# combo_board.net
KiCad netlist of a schematic drawn in EAGLE
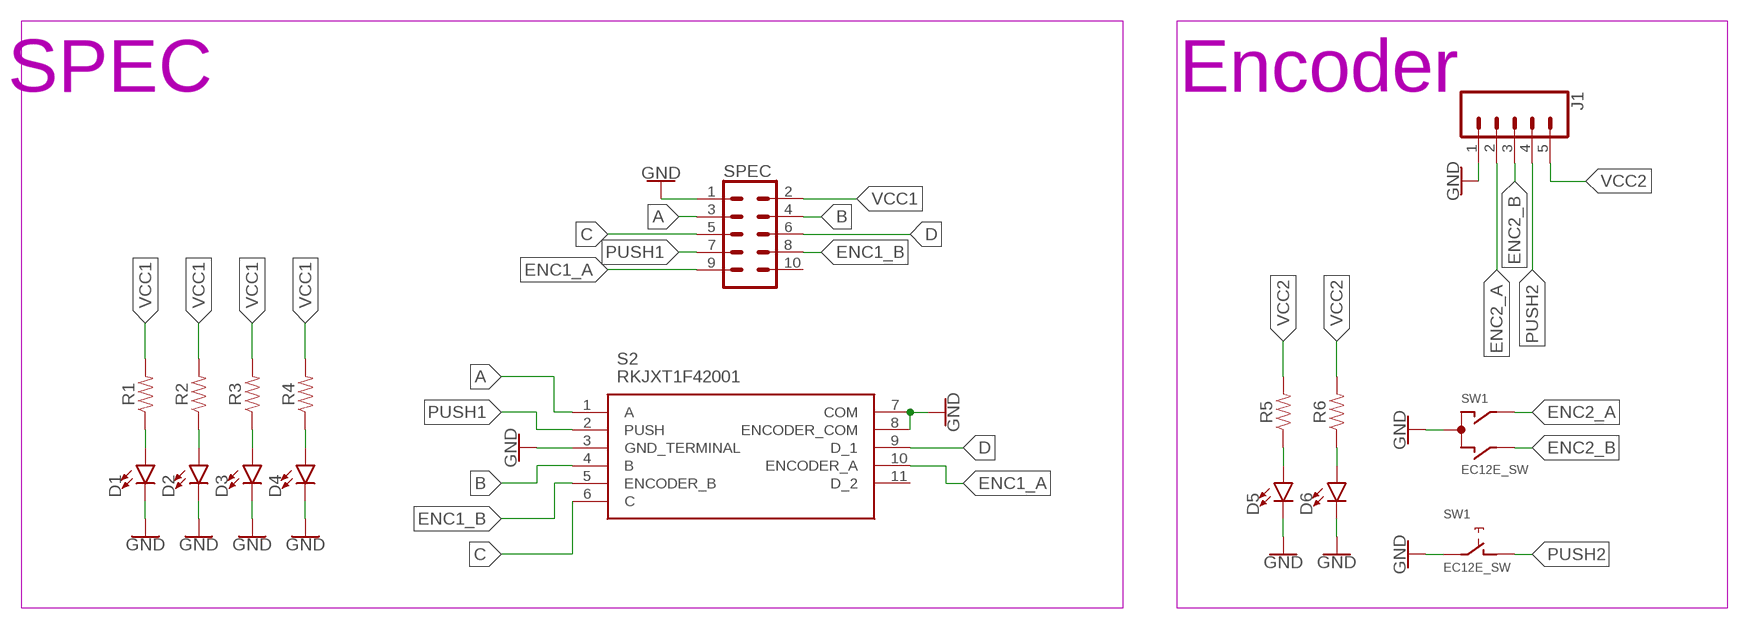
[diagram p0: schematic, sheet 1]

(export (version "E")
  (design (tool "Eeschema 10.0.6"))
  (components
    (comp (ref "D1")
      (value "LED-3MM-NO_SILK")
      (footprint "eagle-import:LED_3MM-NS")
      (libsource (lib "eagle-import") (part "LED-3MM-NO_SILK"))
    )
    (comp (ref "D2")
      (value "LED-3MM-NO_SILK")
      (footprint "eagle-import:LED_3MM-NS")
      (libsource (lib "eagle-import") (part "LED-3MM-NO_SILK"))
    )
    (comp (ref "D3")
      (value "LED-3MM-NO_SILK")
      (footprint "eagle-import:LED_3MM-NS")
      (libsource (lib "eagle-import") (part "LED-3MM-NO_SILK"))
    )
    (comp (ref "D4")
      (value "LED-3MM-NO_SILK")
      (footprint "eagle-import:LED_3MM-NS")
      (libsource (lib "eagle-import") (part "LED-3MM-NO_SILK"))
    )
    (comp (ref "D5")
      (value "LED-3MM-NO_SILK")
      (footprint "eagle-import:LED_3MM-NS")
      (libsource (lib "eagle-import") (part "LED-3MM-NO_SILK"))
    )
    (comp (ref "D6")
      (value "LED-3MM-NO_SILK")
      (footprint "eagle-import:LED_3MM-NS")
      (libsource (lib "eagle-import") (part "LED-3MM-NO_SILK"))
    )
    (comp (ref "J1")
      (value "CONN_05")
      (footprint "eagle-import:1X05")
      (libsource (lib "eagle-import") (part "CONN_05"))
    )
    (comp (ref "R1")
      (value "RESISTOR1206")
      (footprint "eagle-import:1206")
      (libsource (lib "eagle-import") (part "RESISTOR1206"))
    )
    (comp (ref "R2")
      (value "RESISTOR1206")
      (footprint "eagle-import:1206")
      (libsource (lib "eagle-import") (part "RESISTOR1206"))
    )
    (comp (ref "R3")
      (value "RESISTOR1206")
      (footprint "eagle-import:1206")
      (libsource (lib "eagle-import") (part "RESISTOR1206"))
    )
    (comp (ref "R4")
      (value "RESISTOR1206")
      (footprint "eagle-import:1206")
      (libsource (lib "eagle-import") (part "RESISTOR1206"))
    )
    (comp (ref "R5")
      (value "RESISTOR1206")
      (footprint "eagle-import:1206")
      (libsource (lib "eagle-import") (part "RESISTOR1206"))
    )
    (comp (ref "R6")
      (value "RESISTOR1206")
      (footprint "eagle-import:1206")
      (libsource (lib "eagle-import") (part "RESISTOR1206"))
    )
    (comp (ref "S2")
      (value "RKJXT1F42001")
      (footprint "eagle-import:RKJXT1F42001")
      (fields
        (field (name "MOUSER_PART_NUMBER") "688-RKJXT1F42001")
        (field (name "RS_PART_NUMBER") "1239636")
      )
      (libsource (lib "eagle-import") (part "RKJXT1F42001"))
    )
    (comp (ref "SPEC")
      (value "CONN_05X2PTH")
      (footprint "eagle-import:2X5")
      (libsource (lib "eagle-import") (part "CONN_05X2PTH"))
    )
    (comp (ref "SW1")
      (value "EC12E_SW")
      (footprint "eagle-import:ALPS_EC12E_SW")
      (fields (field (name "MPN") "EC12E2424407"))
      (libsource (lib "eagle-import") (part "EC12E_SW"))
    )
  )
  (nets
    (net (code "1") (name "A") (class "Default")
      (node (ref "S2") (pin "1") (pinfunction "A_1") (pintype "bidirectional"))
      (node (ref "SPEC") (pin "3") (pinfunction "3_3") (pintype "passive"))
    )
    (net (code "2") (name "B") (class "Default")
      (node (ref "S2") (pin "4") (pinfunction "B_4") (pintype "bidirectional"))
      (node (ref "SPEC") (pin "4") (pinfunction "4_4") (pintype "passive"))
    )
    (net (code "3") (name "C") (class "Default")
      (node (ref "S2") (pin "6") (pinfunction "C_6") (pintype "bidirectional"))
      (node (ref "SPEC") (pin "5") (pinfunction "5_5") (pintype "passive"))
    )
    (net (code "4") (name "D") (class "Default")
      (node (ref "S2") (pin "9") (pinfunction "D_1_9") (pintype "bidirectional"))
      (node (ref "SPEC") (pin "6") (pinfunction "6_6") (pintype "passive"))
    )
    (net (code "5") (name "ENC1_A") (class "Default")
      (node (ref "S2") (pin "10") (pinfunction "ENCODER_A_10") (pintype "bidirectional"))
      (node (ref "SPEC") (pin "9") (pinfunction "9_9") (pintype "passive"))
    )
    (net (code "6") (name "ENC1_B") (class "Default")
      (node (ref "S2") (pin "5") (pinfunction "ENCODER_B_5") (pintype "bidirectional"))
      (node (ref "SPEC") (pin "8") (pinfunction "8_8") (pintype "passive"))
    )
    (net (code "7") (name "ENC2_A") (class "Default")
      (node (ref "J1") (pin "2") (pinfunction "2_2") (pintype "passive"))
      (node (ref "SW1") (pin "A") (pinfunction "A_A") (pintype "passive"))
    )
    (net (code "8") (name "ENC2_B") (class "Default")
      (node (ref "J1") (pin "3") (pinfunction "3_3") (pintype "passive"))
      (node (ref "SW1") (pin "B") (pinfunction "B_B") (pintype "passive"))
    )
    (net (code "9") (name "GND") (class "Default")
      (node (ref "D1") (pin "K") (pinfunction "C_K") (pintype "passive"))
      (node (ref "D2") (pin "K") (pinfunction "C_K") (pintype "passive"))
      (node (ref "D3") (pin "K") (pinfunction "C_K") (pintype "passive"))
      (node (ref "D4") (pin "K") (pinfunction "C_K") (pintype "passive"))
      (node (ref "D5") (pin "K") (pinfunction "C_K") (pintype "passive"))
      (node (ref "D6") (pin "K") (pinfunction "C_K") (pintype "passive"))
      (node (ref "J1") (pin "1") (pinfunction "1_1") (pintype "passive"))
      (node (ref "S2") (pin "3") (pinfunction "GND_TERMINAL_3") (pintype "bidirectional"))
      (node (ref "S2") (pin "7") (pinfunction "COM_7") (pintype "bidirectional"))
      (node (ref "S2") (pin "8") (pinfunction "ENCODER_COM_8") (pintype "bidirectional"))
      (node (ref "SPEC") (pin "1") (pinfunction "1_1") (pintype "passive"))
      (node (ref "SW1") (pin "C") (pinfunction "C_C") (pintype "passive"))
      (node (ref "SW1") (pin "E") (pinfunction "2_E") (pintype "passive"))
    )
    (net (code "10") (name "Net-(D1-PadA)") (class "Default")
      (node (ref "D1") (pin "A") (pinfunction "A_A") (pintype "passive"))
      (node (ref "R1") (pin "1") (pinfunction "1_1") (pintype "passive"))
    )
    (net (code "11") (name "Net-(D2-PadA)") (class "Default")
      (node (ref "D2") (pin "A") (pinfunction "A_A") (pintype "passive"))
      (node (ref "R2") (pin "1") (pinfunction "1_1") (pintype "passive"))
    )
    (net (code "12") (name "Net-(D3-PadA)") (class "Default")
      (node (ref "D3") (pin "A") (pinfunction "A_A") (pintype "passive"))
      (node (ref "R3") (pin "1") (pinfunction "1_1") (pintype "passive"))
    )
    (net (code "13") (name "Net-(D4-PadA)") (class "Default")
      (node (ref "D4") (pin "A") (pinfunction "A_A") (pintype "passive"))
      (node (ref "R4") (pin "1") (pinfunction "1_1") (pintype "passive"))
    )
    (net (code "14") (name "Net-(D5-PadA)") (class "Default")
      (node (ref "D5") (pin "A") (pinfunction "A_A") (pintype "passive"))
      (node (ref "R5") (pin "1") (pinfunction "1_1") (pintype "passive"))
    )
    (net (code "15") (name "Net-(D6-PadA)") (class "Default")
      (node (ref "D6") (pin "A") (pinfunction "A_A") (pintype "passive"))
      (node (ref "R6") (pin "1") (pinfunction "1_1") (pintype "passive"))
    )
    (net (code "16") (name "PUSH1") (class "Default")
      (node (ref "S2") (pin "2") (pinfunction "PUSH_2") (pintype "bidirectional"))
      (node (ref "SPEC") (pin "7") (pinfunction "7_7") (pintype "passive"))
    )
    (net (code "17") (name "PUSH2") (class "Default")
      (node (ref "J1") (pin "4") (pinfunction "4_4") (pintype "passive"))
      (node (ref "SW1") (pin "D") (pinfunction "1_D") (pintype "passive"))
    )
    (net (code "18") (name "VCC1") (class "Default")
      (node (ref "R1") (pin "2") (pinfunction "2_2") (pintype "passive"))
      (node (ref "R2") (pin "2") (pinfunction "2_2") (pintype "passive"))
      (node (ref "R3") (pin "2") (pinfunction "2_2") (pintype "passive"))
      (node (ref "R4") (pin "2") (pinfunction "2_2") (pintype "passive"))
      (node (ref "SPEC") (pin "2") (pinfunction "2_2") (pintype "passive"))
    )
    (net (code "19") (name "VCC2") (class "Default")
      (node (ref "J1") (pin "5") (pinfunction "5_5") (pintype "passive"))
      (node (ref "R5") (pin "2") (pinfunction "2_2") (pintype "passive"))
      (node (ref "R6") (pin "2") (pinfunction "2_2") (pintype "passive"))
    )
    (net (code "20") (name "unconnected-(S2-D_2-Pad11)") (class "Default")
      (node (ref "S2") (pin "11") (pinfunction "D_2_11") (pintype "bidirectional"))
    )
    (net (code "21") (name "unconnected-(SPEC-Pad10)") (class "Default")
      (node (ref "SPEC") (pin "10") (pinfunction "10_10") (pintype "passive"))
    )
  )
)
